# Spindle_Control.net
KiCad netlist of a schematic drawn in Altium Designer
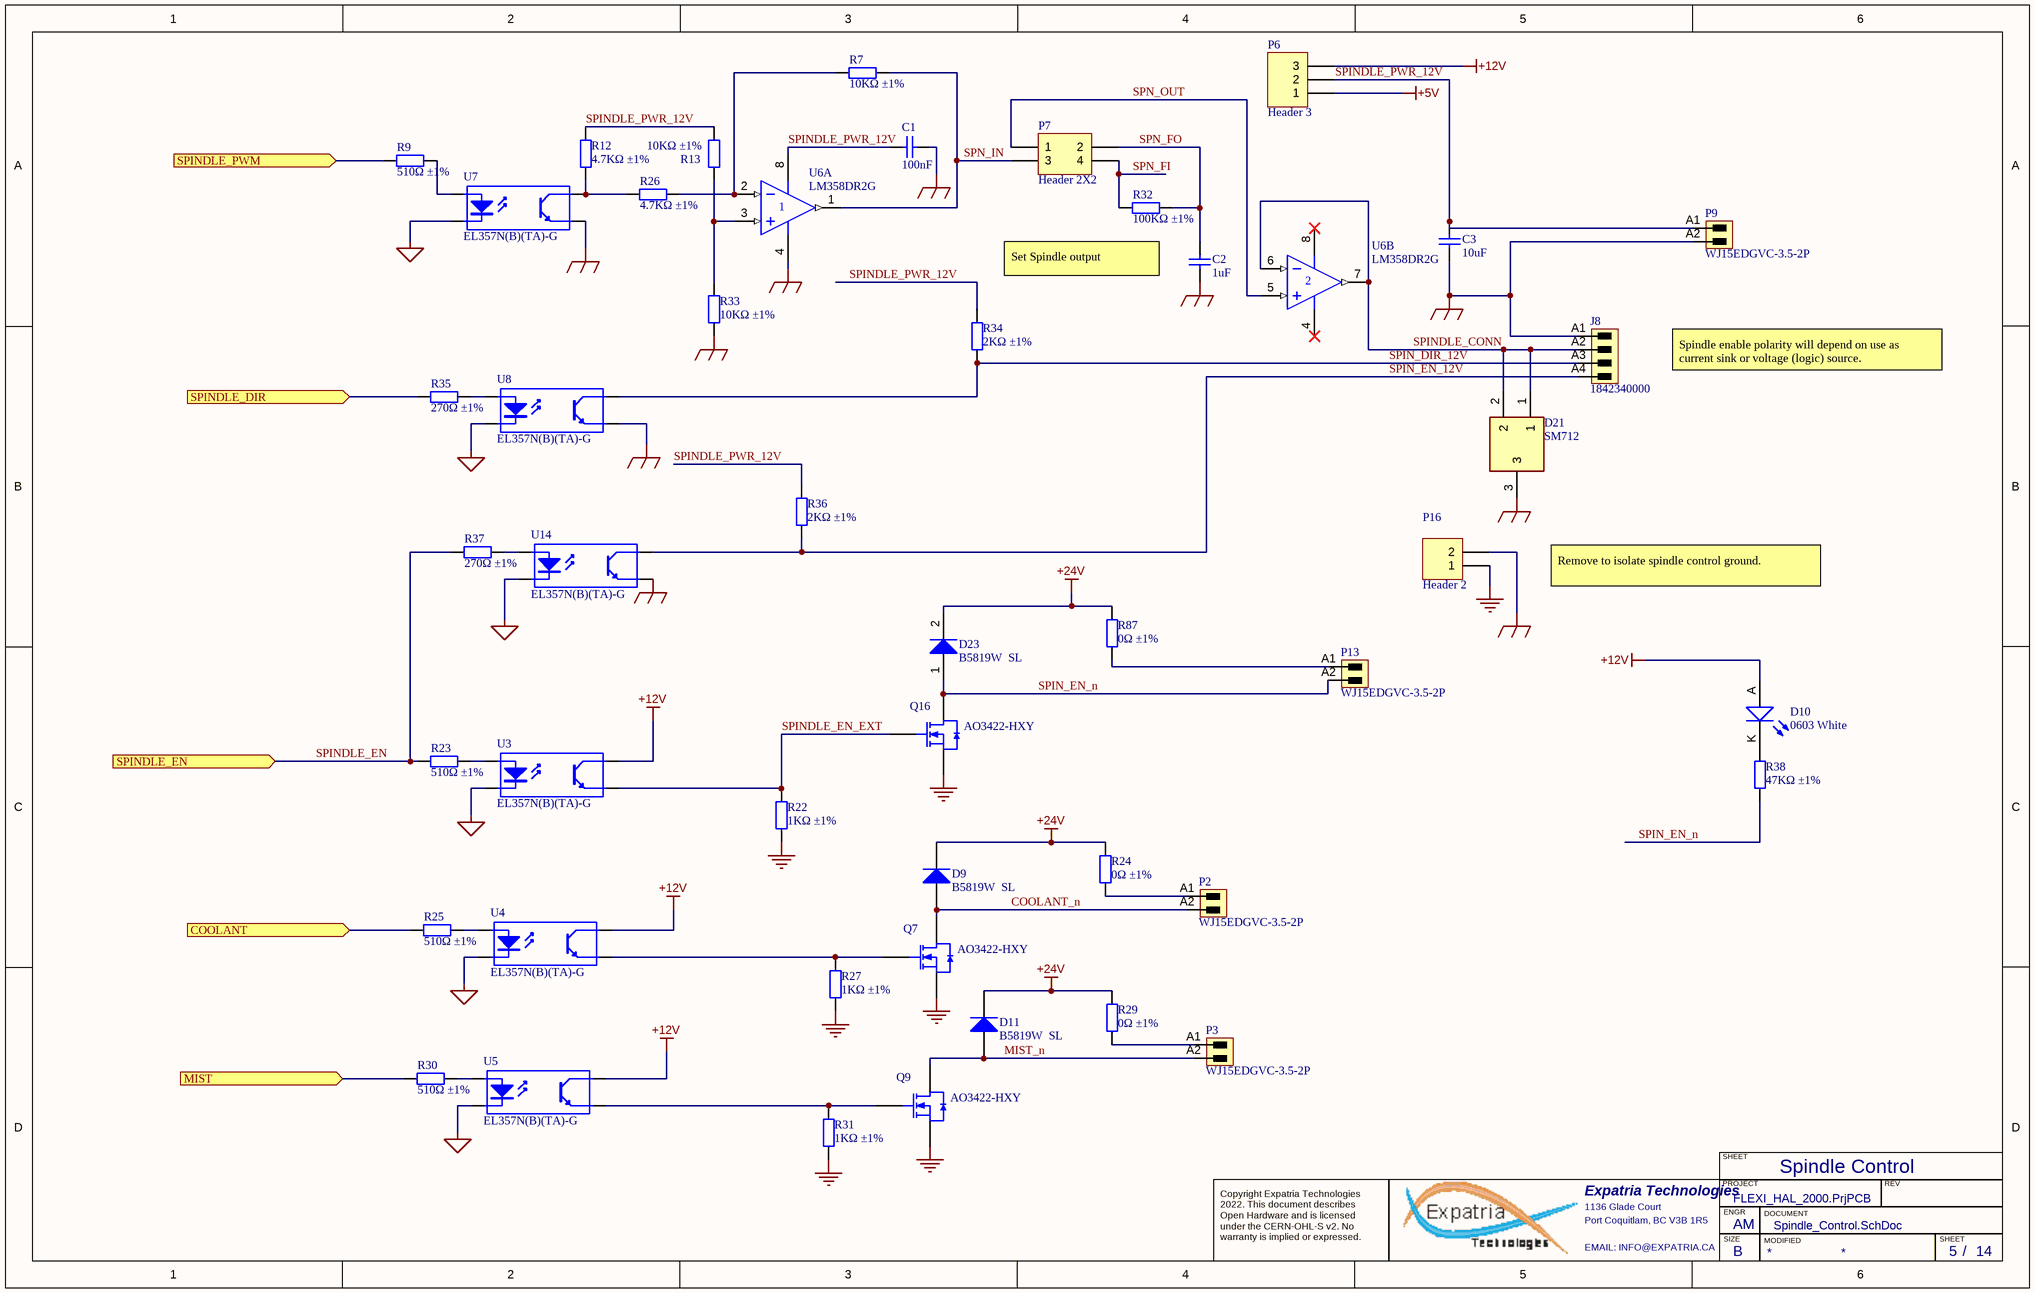
[diagram p0: Spindle_Control.SchDoc]

(export (version "E")
  (design (tool "Eeschema 10.0.6"))
  (components
    (comp (ref "C1")
      (value "100nF")
      (footprint "0603_C")
      (description "Chip capacitors")
      (fields (field (name "MANUFACTURER") "YAGEO") (field (name "PARTNUMBER") "CC0603KRX7R9BB104"))
      (libsource (lib "Cap") (part "0603 100nF (104) 10% 50V"))
    )
    (comp (ref "C2")
      (value "1uF")
      (footprint "0603_C")
      (description "Chip capacitors")
      (fields
        (field (name "MANUFACTURER") "Samsung Electro-Mechanics")
        (field (name "PARTNUMBER") "CL10A105KB8NNNC")
      )
      (libsource (lib "Cap") (part "0603 1uF (105) 10% 50V"))
    )
    (comp (ref "C3")
      (value "10uF")
      (footprint "1206_C")
      (description "Chip capacitors")
      (fields
        (field (name "MANUFACTURER") "Samsung Electro-Mechanics")
        (field (name "PARTNUMBER") "CL31A106KBHNNNE")
      )
      (libsource (lib "Cap") (part "1206 10uF (106) 10% 50V"))
    )
    (comp (ref "D9")
      (value "B5819W  SL")
      (footprint "SOD-123")
      (description "Schottky Diode")
      (libsource (lib "") (part "SOD-123 B5819W  SL_1"))
    )
    (comp (ref "D10")
      (value "0603 White")
      (footprint "0603_LED_S1")
      (description "LED")
      (libsource (lib "LED") (part "0603 LED White"))
    )
    (comp (ref "D11")
      (value "B5819W  SL")
      (footprint "SOD-123")
      (description "Schottky Diode")
      (libsource (lib "") (part "SOD-123 B5819W  SL_1"))
    )
    (comp (ref "D21")
      (value "SM712")
      (footprint "SamacSys:SOT95P230X117-3N")
      (description "Bidirectional 12V (Max), 7V (Max) 7.5V / 13.3V 10V / 20V 12A(8/20us) SOT-23-3 TVS RoHS")
      (libsource (lib "*") (part "CDSOT23-SM712"))
    )
    (comp (ref "D23")
      (value "B5819W  SL")
      (footprint "SOD-123")
      (description "Schottky Diode")
      (libsource (lib "Diode") (part "SOD-123 B5819W  SL"))
    )
    (comp (ref "J8")
      (value "1842340000")
      (footprint "691321100004")
      (description "OMNIMATE Signal - series BL/SL 3.50")
      (libsource (lib "Universal_CNC_Breakout") (part "3.5mm Terminal Header 4p"))
    )
    (comp (ref "P2")
      (value "WJ15EDGVC-3.5-2P")
      (footprint "691321100002")
      (fields (field (name "MANUFACTURER") "Ningbo Kangnex Elec"))
      (libsource (lib "Universal_CNC_Breakout") (part "3.5mm Terminal Header 2p"))
    )
    (comp (ref "P3")
      (value "WJ15EDGVC-3.5-2P")
      (footprint "691321100002")
      (fields (field (name "MANUFACTURER") "Ningbo Kangnex Elec"))
      (libsource (lib "Universal_CNC_Breakout") (part "3.5mm Terminal Header 2p"))
    )
    (comp (ref "P6")
      (value "Header 3")
      (footprint "HDR1X3")
      (description "Header, 3-Pin")
      (fields (field (name "PUBLISHER") "Altium Limited"))
      (libsource (lib "Miscellaneous Connectors") (part "Header 3"))
    )
    (comp (ref "P7")
      (value "Header 2X2")
      (footprint "HDR2X2")
      (description "Header, 2-Pin, Dual row")
      (libsource (lib "Miscellaneous Connectors") (part "Header 2X2"))
    )
    (comp (ref "P9")
      (value "WJ15EDGVC-3.5-2P")
      (footprint "691321100002")
      (fields (field (name "MANUFACTURER") "Ningbo Kangnex Elec"))
      (libsource (lib "Universal_CNC_Breakout") (part "3.5mm Terminal Header 2p"))
    )
    (comp (ref "P13")
      (value "WJ15EDGVC-3.5-2P")
      (footprint "691321100002")
      (fields (field (name "MANUFACTURER") "Ningbo Kangnex Elec"))
      (libsource (lib "Universal_CNC_Breakout") (part "3.5mm Terminal Header 2p"))
    )
    (comp (ref "P16")
      (value "Header 2")
      (footprint "HDR1X2")
      (description "Header, 2-Pin")
      (fields (field (name "PUBLISHER") "Altium Limited"))
      (libsource (lib "Miscellaneous Connectors") (part "Header 2"))
    )
    (comp (ref "Q7")
      (value "AO3422-HXY")
      (footprint "SOT-23-3L")
      (description "60V 4.5A 8W 75mΩ@10V,5A 2.5V@250uA N Channel 695pF@15V SOT-23-3L MOSFETs ROHS")
      (libsource (lib "MOS") (part "AO3400A N道沟 X0YV1T SOT-23"))
    )
    (comp (ref "Q9")
      (value "AO3422-HXY")
      (footprint "SOT-23-3L")
      (description "60V 4.5A 8W 75mΩ@10V,5A 2.5V@250uA N Channel 695pF@15V SOT-23-3L MOSFETs ROHS")
      (libsource (lib "MOS") (part "AO3400A N道沟 X0YV1T SOT-23"))
    )
    (comp (ref "Q16")
      (value "AO3422-HXY")
      (footprint "SOT-23-3L")
      (description "60V 4.5A 8W 75mΩ@10V,5A 2.5V@250uA N Channel 695pF@15V SOT-23-3L MOSFETs ROHS")
      (libsource (lib "MOS") (part "AO3400A N道沟 X0YV1T SOT-23"))
    )
    (comp (ref "R7")
      (value "10KΩ ±1%")
      (footprint "0603_R")
      (description "Chip resistor")
      (fields (field (name "MANUFACTURER") "Uniroyal Elec") (field (name "PARTNUMBER") "0603WAF1002T5E"))
      (libsource (lib "") (part "0603 10K (1002) 1%_1"))
    )
    (comp (ref "R9")
      (value "510Ω ±1%")
      (footprint "0603_R")
      (description "Chip resistor")
      (fields (field (name "MANUFACTURER") "Uniroyal Elec") (field (name "PARTNUMBER") "0603WAF5100T5E"))
      (libsource (lib "RES") (part "0603 510R (5100) 1%"))
    )
    (comp (ref "R12")
      (value "4.7KΩ ±1%")
      (footprint "0603_R")
      (description "Chip resistor")
      (fields (field (name "MANUFACTURER") "Uniroyal Elec") (field (name "PARTNUMBER") "0603WAF4701T5E"))
      (libsource (lib "") (part "0603 4.7K (4701) 1%_1"))
    )
    (comp (ref "R13")
      (value "10KΩ ±1%")
      (footprint "0603_R")
      (description "Chip resistor")
      (fields (field (name "MANUFACTURER") "Uniroyal Elec") (field (name "PARTNUMBER") "0603WAF1002T5E"))
      (libsource (lib "RES") (part "0603 10K (1002) 1%"))
    )
    (comp (ref "R22")
      (value "1KΩ ±1%")
      (footprint "0603_R")
      (description "Chip resistor")
      (fields (field (name "MANUFACTURER") "Uniroyal Elec") (field (name "PARTNUMBER") "0603WAF1001T5E"))
      (libsource (lib "RES") (part "0603 1K (1001) 1%"))
    )
    (comp (ref "R23")
      (value "510Ω ±1%")
      (footprint "0603_R")
      (description "Chip resistor")
      (fields (field (name "MANUFACTURER") "Uniroyal Elec") (field (name "PARTNUMBER") "0603WAF5100T5E"))
      (libsource (lib "RES") (part "0603 510R (5100) 1%"))
    )
    (comp (ref "R24")
      (value "0Ω ±1%")
      (footprint "0603_R")
      (description "Chip resistor")
      (fields (field (name "MANUFACTURER") "Uniroyal Elec") (field (name "PARTNUMBER") "0603WAF0000T5E"))
      (libsource (lib "RES") (part "0603 0R (0R0) 1%"))
    )
    (comp (ref "R25")
      (value "510Ω ±1%")
      (footprint "0603_R")
      (description "Chip resistor")
      (fields (field (name "MANUFACTURER") "Uniroyal Elec") (field (name "PARTNUMBER") "0603WAF5100T5E"))
      (libsource (lib "RES") (part "0603 510R (5100) 1%"))
    )
    (comp (ref "R26")
      (value "4.7KΩ ±1%")
      (footprint "0603_R")
      (description "Chip resistor")
      (fields (field (name "MANUFACTURER") "Uniroyal Elec") (field (name "PARTNUMBER") "0603WAF4701T5E"))
      (libsource (lib "RES") (part "0603 4.7K (4701) 1%"))
    )
    (comp (ref "R27")
      (value "1KΩ ±1%")
      (footprint "0603_R")
      (description "Chip resistor")
      (fields (field (name "MANUFACTURER") "Uniroyal Elec") (field (name "PARTNUMBER") "0603WAF1001T5E"))
      (libsource (lib "RES") (part "0603 1K (1001) 1%"))
    )
    (comp (ref "R29")
      (value "0Ω ±1%")
      (footprint "0603_R")
      (description "Chip resistor")
      (fields (field (name "MANUFACTURER") "Uniroyal Elec") (field (name "PARTNUMBER") "0603WAF0000T5E"))
      (libsource (lib "RES") (part "0603 0R (0R0) 1%"))
    )
    (comp (ref "R30")
      (value "510Ω ±1%")
      (footprint "0603_R")
      (description "Chip resistor")
      (fields (field (name "MANUFACTURER") "Uniroyal Elec") (field (name "PARTNUMBER") "0603WAF5100T5E"))
      (libsource (lib "RES") (part "0603 510R (5100) 1%"))
    )
    (comp (ref "R31")
      (value "1KΩ ±1%")
      (footprint "0603_R")
      (description "Chip resistor")
      (fields (field (name "MANUFACTURER") "Uniroyal Elec") (field (name "PARTNUMBER") "0603WAF1001T5E"))
      (libsource (lib "RES") (part "0603 1K (1001) 1%"))
    )
    (comp (ref "R32")
      (value "100KΩ ±1%")
      (footprint "0603_R")
      (description "Chip resistor")
      (fields (field (name "MANUFACTURER") "Uniroyal Elec") (field (name "PARTNUMBER") "0603WAF1003T5E"))
      (libsource (lib "RES") (part "0603 100K (1003) 1%"))
    )
    (comp (ref "R33")
      (value "10KΩ ±1%")
      (footprint "0603_R")
      (description "Chip resistor")
      (fields (field (name "MANUFACTURER") "Uniroyal Elec") (field (name "PARTNUMBER") "0603WAF1002T5E"))
      (libsource (lib "RES") (part "0603 10K (1002) 1%"))
    )
    (comp (ref "R34")
      (value "2KΩ ±1%")
      (footprint "0603_R")
      (description "Chip resistor")
      (fields (field (name "MANUFACTURER") "Uniroyal Elec") (field (name "PARTNUMBER") "0603WAF2001T5E"))
      (libsource (lib "RES") (part "0603 2K (2001) 1%"))
    )
    (comp (ref "R35")
      (value "270Ω ±1%")
      (footprint "0603_R")
      (description "Chip resistor")
      (fields (field (name "MANUFACTURER") "Uniroyal Elec") (field (name "PARTNUMBER") "0603WAF2700T5E"))
      (libsource (lib "RES") (part "0603 270R (2700) 1%"))
    )
    (comp (ref "R36")
      (value "2KΩ ±1%")
      (footprint "0603_R")
      (description "Chip resistor")
      (fields (field (name "MANUFACTURER") "Uniroyal Elec") (field (name "PARTNUMBER") "0603WAF2001T5E"))
      (libsource (lib "RES") (part "0603 2K (2001) 1%"))
    )
    (comp (ref "R37")
      (value "270Ω ±1%")
      (footprint "0603_R")
      (description "Chip resistor")
      (fields (field (name "MANUFACTURER") "Uniroyal Elec") (field (name "PARTNUMBER") "0603WAF2700T5E"))
      (libsource (lib "RES") (part "0603 270R (2700) 1%"))
    )
    (comp (ref "R38")
      (value "47KΩ ±1%")
      (footprint "0603_R")
      (description "Chip resistor")
      (fields (field (name "MANUFACTURER") "Uniroyal Elec") (field (name "PARTNUMBER") "0603WAF4702T5E"))
      (libsource (lib "RES") (part "0603 47K (4702) 1%"))
    )
    (comp (ref "R87")
      (value "0Ω ±1%")
      (footprint "0603_R")
      (description "Chip resistor")
      (fields (field (name "MANUFACTURER") "Uniroyal Elec") (field (name "PARTNUMBER") "0603WAF0000T5E"))
      (libsource (lib "RES") (part "0603 0R (0R0) 1%"))
    )
    (comp (ref "U3")
      (value "EL357N(B)(TA)-G")
      (footprint "Miscellaneous Devices LC:SOP-4_P2.54")
      (description "OPTOISOLATOR 3.75KV TRANS 4-SOP")
      (libsource (lib "IC") (part "EL357N(B)(TA)-G_[C6649]"))
    )
    (comp (ref "U4")
      (value "EL357N(B)(TA)-G")
      (footprint "Miscellaneous Devices LC:SOP-4_P2.54")
      (description "OPTOISOLATOR 3.75KV TRANS 4-SOP")
      (libsource (lib "IC") (part "EL357N(B)(TA)-G_[C6649]"))
    )
    (comp (ref "U5")
      (value "EL357N(B)(TA)-G")
      (footprint "Miscellaneous Devices LC:SOP-4_P2.54")
      (description "OPTOISOLATOR 3.75KV TRANS 4-SOP")
      (libsource (lib "IC") (part "EL357N(B)(TA)-G_[C6649]"))
    )
    (comp (ref "U6")
      (value "LM358DR2G")
      (footprint "SOIC-8_150mil")
      (description "Dual Op Amp,  5 - 28 V,  8-PinSOIC")
      (libsource (lib "PrintNC_GRBLHAL_Breakout") (part "LM358DR2G_[C7950]"))
    )
    (comp (ref "U7")
      (value "EL357N(B)(TA)-G")
      (footprint "Miscellaneous Devices LC:SOP-4_P2.54")
      (description "OPTOISOLATOR 3.75KV TRANS 4-SOP")
      (libsource (lib "PrintNC_GRBLHAL_Breakout") (part "EL357N(B)(TA)-G_[C6649]"))
    )
    (comp (ref "U8")
      (value "EL357N(B)(TA)-G")
      (footprint "Miscellaneous Devices LC:SOP-4_P2.54")
      (description "OPTOISOLATOR 3.75KV TRANS 4-SOP")
      (libsource (lib "PrintNC_GRBLHAL_Breakout") (part "EL357N(B)(TA)-G_[C6649]"))
    )
    (comp (ref "U14")
      (value "EL357N(B)(TA)-G")
      (footprint "Miscellaneous Devices LC:SOP-4_P2.54")
      (description "OPTOISOLATOR 3.75KV TRANS 4-SOP")
      (libsource (lib "PrintNC_GRBLHAL_Breakout") (part "EL357N(B)(TA)-G_[C6649]"))
    )
  )
  (nets
    (net (code "1") (name "+5V") (class "Default")
      (node (ref "P6") (pin "1") (pinfunction "1_1") (pintype "passive"))
    )
    (net (code "2") (name "+12V") (class "Default")
      (node (ref "D10") (pin "A") (pinfunction "A_A") (pintype "passive"))
      (node (ref "P6") (pin "3") (pinfunction "3_3") (pintype "passive"))
      (node (ref "U3") (pin "4") (pinfunction "C_4") (pintype "passive"))
      (node (ref "U4") (pin "4") (pinfunction "C_4") (pintype "passive"))
      (node (ref "U5") (pin "4") (pinfunction "C_4") (pintype "passive"))
    )
    (net (code "3") (name "+24V") (class "Default")
      (node (ref "D11") (pin "2") (pinfunction "K_2") (pintype "passive"))
      (node (ref "D23") (pin "2") (pinfunction "K_2") (pintype "passive"))
      (node (ref "D9") (pin "2") (pinfunction "K_2") (pintype "passive"))
      (node (ref "R24") (pin "1") (pinfunction "1_1") (pintype "passive"))
      (node (ref "R29") (pin "1") (pinfunction "1_1") (pintype "passive"))
      (node (ref "R87") (pin "1") (pinfunction "1_1") (pintype "passive"))
    )
    (net (code "4") (name "/COOLANT") (class "Default")
      (node (ref "R25") (pin "1") (pinfunction "1_1") (pintype "passive"))
    )
    (net (code "5") (name "/COOLANT_n") (class "Default")
      (node (ref "D9") (pin "1") (pinfunction "A_1") (pintype "passive"))
      (node (ref "P2") (pin "A2") (pinfunction "A2_A2") (pintype "passive"))
      (node (ref "Q7") (pin "3") (pinfunction "D_3") (pintype "passive"))
    )
    (net (code "6") (name "/MIST") (class "Default")
      (node (ref "R30") (pin "1") (pinfunction "1_1") (pintype "passive"))
    )
    (net (code "7") (name "/MIST_n") (class "Default")
      (node (ref "D11") (pin "1") (pinfunction "A_1") (pintype "passive"))
      (node (ref "P3") (pin "A2") (pinfunction "A2_A2") (pintype "passive"))
      (node (ref "Q9") (pin "3") (pinfunction "D_3") (pintype "passive"))
    )
    (net (code "8") (name "/SPINDLE_CONN") (class "Default")
      (node (ref "D21") (pin "1") (pinfunction "1_1") (pintype "passive"))
      (node (ref "D21") (pin "2") (pinfunction "2_2") (pintype "passive"))
      (node (ref "J8") (pin "A2") (pinfunction "A2_A2") (pintype "passive"))
      (node (ref "U6") (pin "6") (pinfunction "IN-_6") (pintype "input"))
      (node (ref "U6") (pin "7") (pinfunction "OUT_7") (pintype "output"))
    )
    (net (code "9") (name "/SPINDLE_DIR") (class "Default")
      (node (ref "R35") (pin "1") (pinfunction "1_1") (pintype "passive"))
    )
    (net (code "10") (name "/SPINDLE_EN") (class "Default")
      (node (ref "R23") (pin "1") (pinfunction "1_1") (pintype "passive"))
      (node (ref "R37") (pin "1") (pinfunction "1_1") (pintype "passive"))
    )
    (net (code "11") (name "/SPINDLE_EN_EXT") (class "Default")
      (node (ref "Q16") (pin "1") (pinfunction "G_1") (pintype "passive"))
      (node (ref "R22") (pin "2") (pinfunction "2_2") (pintype "passive"))
      (node (ref "U3") (pin "3") (pinfunction "E_3") (pintype "passive"))
    )
    (net (code "12") (name "/SPINDLE_PWM") (class "Default")
      (node (ref "R9") (pin "1") (pinfunction "1_1") (pintype "passive"))
    )
    (net (code "13") (name "/SPINDLE_PWR_12V") (class "Default")
      (node (ref "C1") (pin "2") (pinfunction "2_2") (pintype "passive"))
      (node (ref "C3") (pin "2") (pinfunction "2_2") (pintype "passive"))
      (node (ref "P6") (pin "2") (pinfunction "2_2") (pintype "passive"))
      (node (ref "P9") (pin "A1") (pinfunction "A1_A1") (pintype "passive"))
      (node (ref "R12") (pin "1") (pinfunction "1_1") (pintype "passive"))
      (node (ref "R13") (pin "1") (pinfunction "1_1") (pintype "passive"))
      (node (ref "R34") (pin "2") (pinfunction "2_2") (pintype "passive"))
      (node (ref "R36") (pin "2") (pinfunction "2_2") (pintype "passive"))
      (node (ref "U6") (pin "8") (pinfunction "V+_8") (pintype "power_in"))
    )
    (net (code "14") (name "/SPIN_DIR_12V") (class "Default")
      (node (ref "J8") (pin "A3") (pinfunction "A3_A3") (pintype "passive"))
      (node (ref "R34") (pin "1") (pinfunction "1_1") (pintype "passive"))
      (node (ref "U8") (pin "4") (pinfunction "C_4") (pintype "passive"))
    )
    (net (code "15") (name "/SPIN_EN_12V") (class "Default")
      (node (ref "J8") (pin "A4") (pinfunction "A4_A4") (pintype "passive"))
      (node (ref "R36") (pin "1") (pinfunction "1_1") (pintype "passive"))
      (node (ref "U14") (pin "4") (pinfunction "C_4") (pintype "passive"))
    )
    (net (code "16") (name "/SPIN_EN_n") (class "Default")
      (node (ref "D23") (pin "1") (pinfunction "A_1") (pintype "passive"))
      (node (ref "P13") (pin "A2") (pinfunction "A2_A2") (pintype "passive"))
      (node (ref "Q16") (pin "3") (pinfunction "D_3") (pintype "passive"))
      (node (ref "R38") (pin "1") (pinfunction "1_1") (pintype "passive"))
    )
    (net (code "17") (name "/SPN_FI") (class "Default")
      (node (ref "P7") (pin "4") (pinfunction "4_4") (pintype "passive"))
      (node (ref "R32") (pin "2") (pinfunction "2_2") (pintype "passive"))
    )
    (net (code "18") (name "/SPN_FO") (class "Default")
      (node (ref "C2") (pin "2") (pinfunction "2_2") (pintype "passive"))
      (node (ref "P7") (pin "2") (pinfunction "2_2") (pintype "passive"))
      (node (ref "R32") (pin "1") (pinfunction "1_1") (pintype "passive"))
    )
    (net (code "19") (name "/SPN_IN") (class "Default")
      (node (ref "P7") (pin "3") (pinfunction "3_3") (pintype "passive"))
      (node (ref "R7") (pin "2") (pinfunction "2_2") (pintype "passive"))
      (node (ref "U6") (pin "1") (pinfunction "OUT_1") (pintype "output"))
    )
    (net (code "20") (name "/SPN_OUT") (class "Default")
      (node (ref "P7") (pin "1") (pinfunction "1_1") (pintype "passive"))
      (node (ref "U6") (pin "5") (pinfunction "IN+_5") (pintype "input"))
    )
    (net (code "21") (name "GND") (class "Default")
      (node (ref "P16") (pin "1") (pinfunction "1_1") (pintype "passive"))
      (node (ref "Q16") (pin "2") (pinfunction "S_2") (pintype "passive"))
      (node (ref "Q7") (pin "2") (pinfunction "S_2") (pintype "passive"))
      (node (ref "Q9") (pin "2") (pinfunction "S_2") (pintype "passive"))
      (node (ref "R22") (pin "1") (pinfunction "1_1") (pintype "passive"))
      (node (ref "R27") (pin "1") (pinfunction "1_1") (pintype "passive"))
      (node (ref "R31") (pin "1") (pinfunction "1_1") (pintype "passive"))
    )
    (net (code "22") (name "MCU_GND") (class "Default")
      (node (ref "U14") (pin "2") (pinfunction "K_2") (pintype "passive"))
      (node (ref "U3") (pin "2") (pinfunction "K_2") (pintype "passive"))
      (node (ref "U4") (pin "2") (pinfunction "K_2") (pintype "passive"))
      (node (ref "U5") (pin "2") (pinfunction "K_2") (pintype "passive"))
      (node (ref "U7") (pin "2") (pinfunction "K_2") (pintype "passive"))
      (node (ref "U8") (pin "2") (pinfunction "K_2") (pintype "passive"))
    )
    (net (code "23") (name "Net-(D10-PadK)") (class "Default")
      (node (ref "D10") (pin "K") (pinfunction "K_K") (pintype "passive"))
      (node (ref "R38") (pin "2") (pinfunction "2_2") (pintype "passive"))
    )
    (net (code "24") (name "Net-(P2-PadA1)") (class "Default")
      (node (ref "P2") (pin "A1") (pinfunction "A1_A1") (pintype "passive"))
      (node (ref "R24") (pin "2") (pinfunction "2_2") (pintype "passive"))
    )
    (net (code "25") (name "Net-(P3-PadA1)") (class "Default")
      (node (ref "P3") (pin "A1") (pinfunction "A1_A1") (pintype "passive"))
      (node (ref "R29") (pin "2") (pinfunction "2_2") (pintype "passive"))
    )
    (net (code "26") (name "Net-(P13-PadA1)") (class "Default")
      (node (ref "P13") (pin "A1") (pinfunction "A1_A1") (pintype "passive"))
      (node (ref "R87") (pin "2") (pinfunction "2_2") (pintype "passive"))
    )
    (net (code "27") (name "Net-(Q7-G)") (class "Default")
      (node (ref "Q7") (pin "1") (pinfunction "G_1") (pintype "passive"))
      (node (ref "R27") (pin "2") (pinfunction "2_2") (pintype "passive"))
      (node (ref "U4") (pin "3") (pinfunction "E_3") (pintype "passive"))
    )
    (net (code "28") (name "Net-(Q9-G)") (class "Default")
      (node (ref "Q9") (pin "1") (pinfunction "G_1") (pintype "passive"))
      (node (ref "R31") (pin "2") (pinfunction "2_2") (pintype "passive"))
      (node (ref "U5") (pin "3") (pinfunction "E_3") (pintype "passive"))
    )
    (net (code "29") (name "Net-(U3-A)") (class "Default")
      (node (ref "R23") (pin "2") (pinfunction "2_2") (pintype "passive"))
      (node (ref "U3") (pin "1") (pinfunction "A_1") (pintype "passive"))
    )
    (net (code "30") (name "Net-(U4-A)") (class "Default")
      (node (ref "R25") (pin "2") (pinfunction "2_2") (pintype "passive"))
      (node (ref "U4") (pin "1") (pinfunction "A_1") (pintype "passive"))
    )
    (net (code "31") (name "Net-(U5-A)") (class "Default")
      (node (ref "R30") (pin "2") (pinfunction "2_2") (pintype "passive"))
      (node (ref "U5") (pin "1") (pinfunction "A_1") (pintype "passive"))
    )
    (net (code "32") (name "Net-(U6A-IN+)") (class "Default")
      (node (ref "R13") (pin "2") (pinfunction "2_2") (pintype "passive"))
      (node (ref "R33") (pin "1") (pinfunction "1_1") (pintype "passive"))
      (node (ref "U6") (pin "3") (pinfunction "IN+_3") (pintype "input"))
    )
    (net (code "33") (name "Net-(U6A-IN-)") (class "Default")
      (node (ref "R26") (pin "2") (pinfunction "2_2") (pintype "passive"))
      (node (ref "R7") (pin "1") (pinfunction "1_1") (pintype "passive"))
      (node (ref "U6") (pin "2") (pinfunction "IN-_2") (pintype "input"))
    )
    (net (code "34") (name "Net-(U7-A)") (class "Default")
      (node (ref "R9") (pin "2") (pinfunction "2_2") (pintype "passive"))
      (node (ref "U7") (pin "1") (pinfunction "A_1") (pintype "passive"))
    )
    (net (code "35") (name "Net-(U7-C)") (class "Default")
      (node (ref "R12") (pin "2") (pinfunction "2_2") (pintype "passive"))
      (node (ref "R26") (pin "1") (pinfunction "1_1") (pintype "passive"))
      (node (ref "U7") (pin "4") (pinfunction "C_4") (pintype "passive"))
    )
    (net (code "36") (name "Net-(U8-A)") (class "Default")
      (node (ref "R35") (pin "2") (pinfunction "2_2") (pintype "passive"))
      (node (ref "U8") (pin "1") (pinfunction "A_1") (pintype "passive"))
    )
    (net (code "37") (name "Net-(U14-A)") (class "Default")
      (node (ref "R37") (pin "2") (pinfunction "2_2") (pintype "passive"))
      (node (ref "U14") (pin "1") (pinfunction "A_1") (pintype "passive"))
    )
    (net (code "38") (name "SPIN_GND") (class "Default")
      (node (ref "C1") (pin "1") (pinfunction "1_1") (pintype "passive"))
      (node (ref "C2") (pin "1") (pinfunction "1_1") (pintype "passive"))
      (node (ref "C3") (pin "1") (pinfunction "1_1") (pintype "passive"))
      (node (ref "D21") (pin "3") (pinfunction "3_3") (pintype "passive"))
      (node (ref "J8") (pin "A1") (pinfunction "A1_A1") (pintype "passive"))
      (node (ref "P16") (pin "2") (pinfunction "2_2") (pintype "passive"))
      (node (ref "P9") (pin "A2") (pinfunction "A2_A2") (pintype "passive"))
      (node (ref "R33") (pin "2") (pinfunction "2_2") (pintype "passive"))
      (node (ref "U14") (pin "3") (pinfunction "E_3") (pintype "passive"))
      (node (ref "U6") (pin "4") (pinfunction "V-_4") (pintype "power_in"))
      (node (ref "U7") (pin "3") (pinfunction "E_3") (pintype "passive"))
      (node (ref "U8") (pin "3") (pinfunction "E_3") (pintype "passive"))
    )
    (net (code "39") (name "unconnected-(U6B-V+-Pad8)") (class "Default")
      (node (ref "U6") (pin "8") (pinfunction "V+_8") (pintype "power_in+no_connect"))
    )
    (net (code "40") (name "unconnected-(U6B-V--Pad4)") (class "Default")
      (node (ref "U6") (pin "4") (pinfunction "V-_4") (pintype "power_in+no_connect"))
    )
  )
)
